# Shiym_Solar_Panel_3U_Rev2_1.net
KiCad netlist of a schematic drawn in Altium Designer
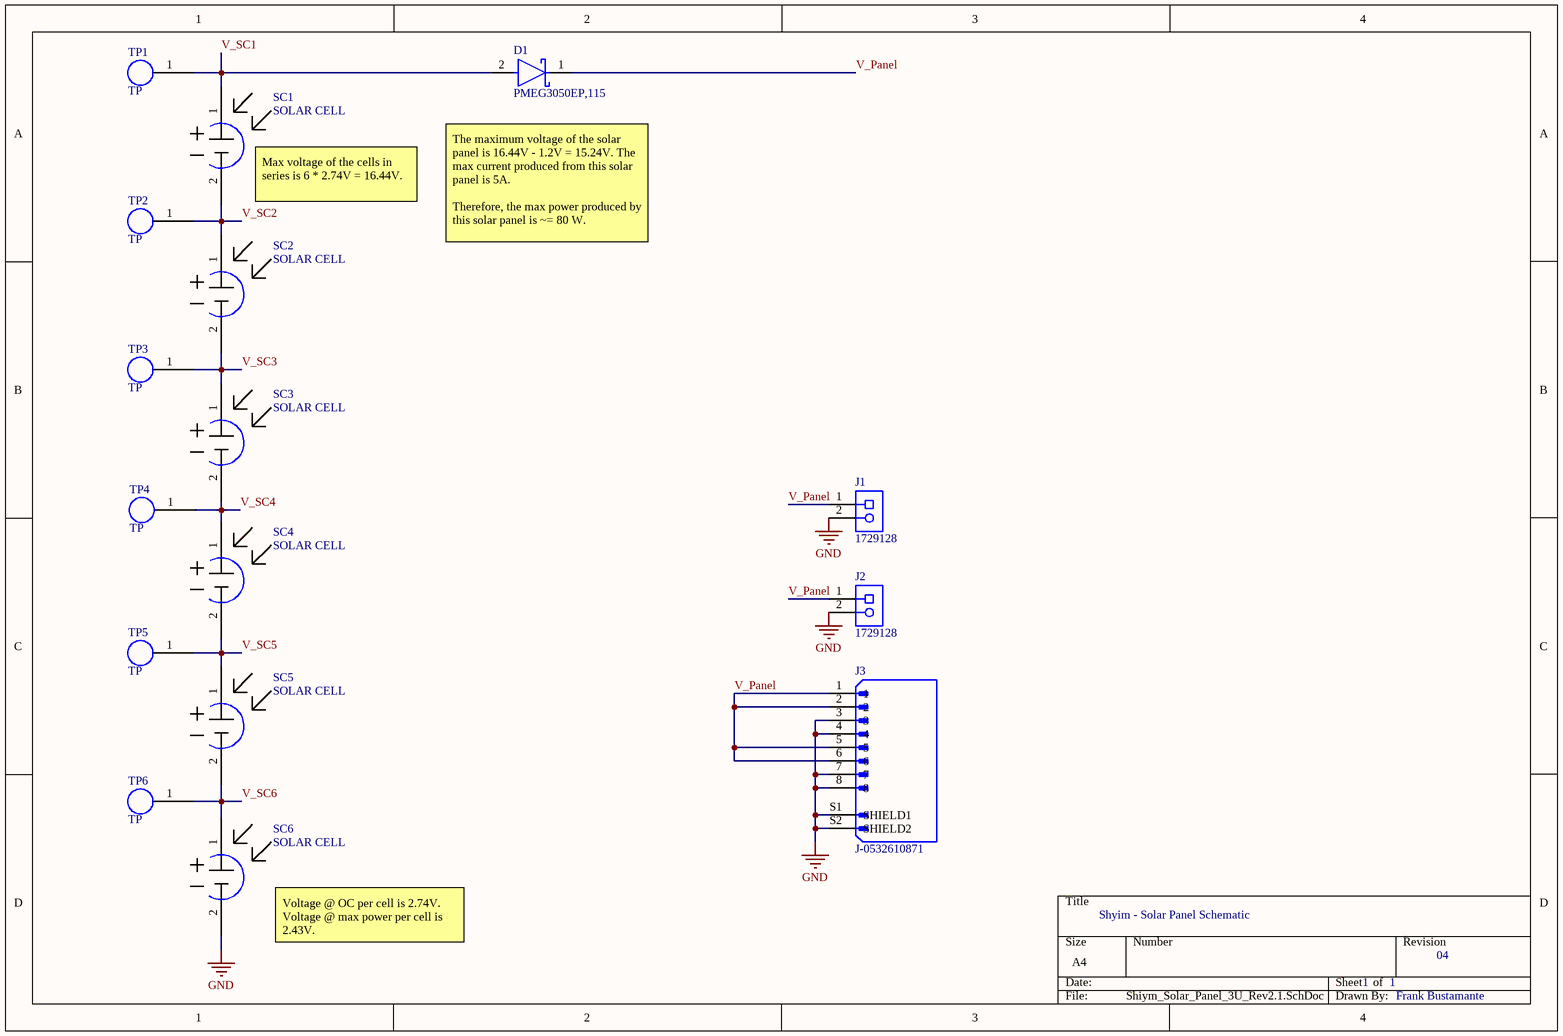
[diagram p0: Shiym_Solar_Panel_3U_Rev2.1.SchDoc]

(export (version "E")
  (design (tool "Eeschema 10.0.6"))
  (components
    (comp (ref "D1")
      (value "PMEG3050EP,115")
      (footprint "FP-SOD128-MFG")
      (description "DIODE SCHOTTKY 30V 5A SOD128")
      (libsource (lib "Altium Content Vault") (part "1d6ec82d83fb6aee721767c19dac4b9"))
    )
    (comp (ref "J1")
      (value "1729128")
      (footprint "PHOE-1729128-2_V")
      (description "PCB Terminal Block, 13.5 A, 400 V, 2-Pin THD, RoHS, Bulk")
      (fields
        (field (name "MANUFACTURER") "Phoenix Contact")
        (field (name "SAFETY APPROVAL") "CSA,CUL,CB,EAC")
      )
      (libsource (lib "Altium Content Vault") (part "CN-2P-F-R2"))
    )
    (comp (ref "J2")
      (value "1729128")
      (footprint "PHOE-1729128-2_V")
      (description "PCB Terminal Block, 13.5 A, 400 V, 2-Pin THD, RoHS, Bulk")
      (fields
        (field (name "MANUFACTURER") "Phoenix Contact")
        (field (name "SAFETY APPROVAL") "CSA,CUL,CB,EAC")
      )
      (libsource (lib "Altium Content Vault") (part "CN-2P-F-R2"))
    )
    (comp (ref "J3")
      (value "J-0532610871")
      (footprint "J-532610871")
      (description "CONN HEADER SMD R/A 8POS 1.25MM")
      (fields
        (field (name "MANFACTURER PART #") "0532610871")
        (field (name "DISTRIBUTOR PART #") "WM7626CT-ND")
      )
      (libsource (lib "OBC Development Board") (part "J-0532610871"))
    )
    (comp (ref "SC1")
      (value "SOLAR CELL")
      (footprint "SOL_CEL_SHYIM")
      (description "Solar Cell from Shyim")
      (fields (field (name "INTERNALPART#") "SC-3GA-3"))
      (libsource (lib "Schlib3") (part "SOL_CEL_SHYIM"))
    )
    (comp (ref "SC2")
      (value "SOLAR CELL")
      (footprint "SOL_CEL_SHYIM")
      (description "Solar Cell from Shyim")
      (fields (field (name "INTERNALPART#") "SC-3GA-3"))
      (libsource (lib "Schlib3") (part "SOL_CEL_SHYIM"))
    )
    (comp (ref "SC3")
      (value "SOLAR CELL")
      (footprint "SOL_CEL_SHYIM")
      (description "Solar Cell from Shyim")
      (fields (field (name "INTERNALPART#") "SC-3GA-3"))
      (libsource (lib "Schlib3") (part "SOL_CEL_SHYIM"))
    )
    (comp (ref "SC4")
      (value "SOLAR CELL")
      (footprint "SOL_CEL_SHYIM")
      (description "Solar Cell from Shyim")
      (fields (field (name "INTERNALPART#") "SC-3GA-3"))
      (libsource (lib "Schlib3") (part "SOL_CEL_SHYIM"))
    )
    (comp (ref "SC5")
      (value "SOLAR CELL")
      (footprint "SOL_CEL_SHYIM")
      (description "Solar Cell from Shyim")
      (fields (field (name "INTERNALPART#") "SC-3GA-3"))
      (libsource (lib "Schlib3") (part "SOL_CEL_SHYIM"))
    )
    (comp (ref "SC6")
      (value "SOLAR CELL")
      (footprint "SOL_CEL_SHYIM")
      (description "Solar Cell from Shyim")
      (fields (field (name "INTERNALPART#") "SC-3GA-3"))
      (libsource (lib "Schlib3") (part "SOL_CEL_SHYIM"))
    )
    (comp (ref "TP1") (value "TP") (footprint "TP") (libsource (lib "Schlib3") (part "TP")))
    (comp (ref "TP2") (value "TP") (footprint "TP") (libsource (lib "Schlib3") (part "TP")))
    (comp (ref "TP3") (value "TP") (footprint "TP") (libsource (lib "Schlib3") (part "TP")))
    (comp (ref "TP4") (value "TP") (footprint "TP") (libsource (lib "Schlib3") (part "TP")))
    (comp (ref "TP5") (value "TP") (footprint "TP") (libsource (lib "Schlib3") (part "TP")))
    (comp (ref "TP6") (value "TP") (footprint "TP") (libsource (lib "Schlib3") (part "TP")))
  )
  (nets
    (net (code "1") (name "/V_Panel") (class "Default")
      (node (ref "D1") (pin "1") (pinfunction "C_1") (pintype "passive"))
      (node (ref "J1") (pin "1") (pinfunction "1_1") (pintype "passive"))
      (node (ref "J2") (pin "1") (pinfunction "1_1") (pintype "passive"))
      (node (ref "J3") (pin "1") (pinfunction "1_1") (pintype "passive"))
      (node (ref "J3") (pin "2") (pinfunction "2_2") (pintype "passive"))
      (node (ref "J3") (pin "5") (pinfunction "5_5") (pintype "passive"))
      (node (ref "J3") (pin "6") (pinfunction "6_6") (pintype "passive"))
    )
    (net (code "2") (name "/V_SC1") (class "Default")
      (node (ref "D1") (pin "2") (pinfunction "A_2") (pintype "passive"))
      (node (ref "SC1") (pin "1") (pinfunction "1_1") (pintype "passive"))
      (node (ref "TP1") (pin "1") (pinfunction "1_1") (pintype "passive"))
    )
    (net (code "3") (name "/V_SC2") (class "Default")
      (node (ref "SC1") (pin "2") (pinfunction "2_2") (pintype "passive"))
      (node (ref "SC2") (pin "1") (pinfunction "1_1") (pintype "passive"))
      (node (ref "TP2") (pin "1") (pinfunction "1_1") (pintype "passive"))
    )
    (net (code "4") (name "/V_SC3") (class "Default")
      (node (ref "SC2") (pin "2") (pinfunction "2_2") (pintype "passive"))
      (node (ref "SC3") (pin "1") (pinfunction "1_1") (pintype "passive"))
      (node (ref "TP3") (pin "1") (pinfunction "1_1") (pintype "passive"))
    )
    (net (code "5") (name "/V_SC4") (class "Default")
      (node (ref "SC3") (pin "2") (pinfunction "2_2") (pintype "passive"))
      (node (ref "SC4") (pin "1") (pinfunction "1_1") (pintype "passive"))
      (node (ref "TP4") (pin "1") (pinfunction "1_1") (pintype "passive"))
    )
    (net (code "6") (name "/V_SC5") (class "Default")
      (node (ref "SC4") (pin "2") (pinfunction "2_2") (pintype "passive"))
      (node (ref "SC5") (pin "1") (pinfunction "1_1") (pintype "passive"))
      (node (ref "TP5") (pin "1") (pinfunction "1_1") (pintype "passive"))
    )
    (net (code "7") (name "/V_SC6") (class "Default")
      (node (ref "SC5") (pin "2") (pinfunction "2_2") (pintype "passive"))
      (node (ref "SC6") (pin "1") (pinfunction "1_1") (pintype "passive"))
      (node (ref "TP6") (pin "1") (pinfunction "1_1") (pintype "passive"))
    )
    (net (code "8") (name "GND") (class "Default")
      (node (ref "J1") (pin "2") (pinfunction "2_2") (pintype "passive"))
      (node (ref "J2") (pin "2") (pinfunction "2_2") (pintype "passive"))
      (node (ref "J3") (pin "3") (pinfunction "3_3") (pintype "passive"))
      (node (ref "J3") (pin "4") (pinfunction "4_4") (pintype "passive"))
      (node (ref "J3") (pin "7") (pinfunction "7_7") (pintype "passive"))
      (node (ref "J3") (pin "8") (pinfunction "8_8") (pintype "passive"))
      (node (ref "J3") (pin "S1") (pinfunction "SHIELD1_S1") (pintype "passive"))
      (node (ref "J3") (pin "S2") (pinfunction "SHIELD2_S2") (pintype "passive"))
      (node (ref "SC6") (pin "2") (pinfunction "2_2") (pintype "passive"))
    )
  )
)
